# main.net
KiCad netlist of a schematic drawn in Altium Designer
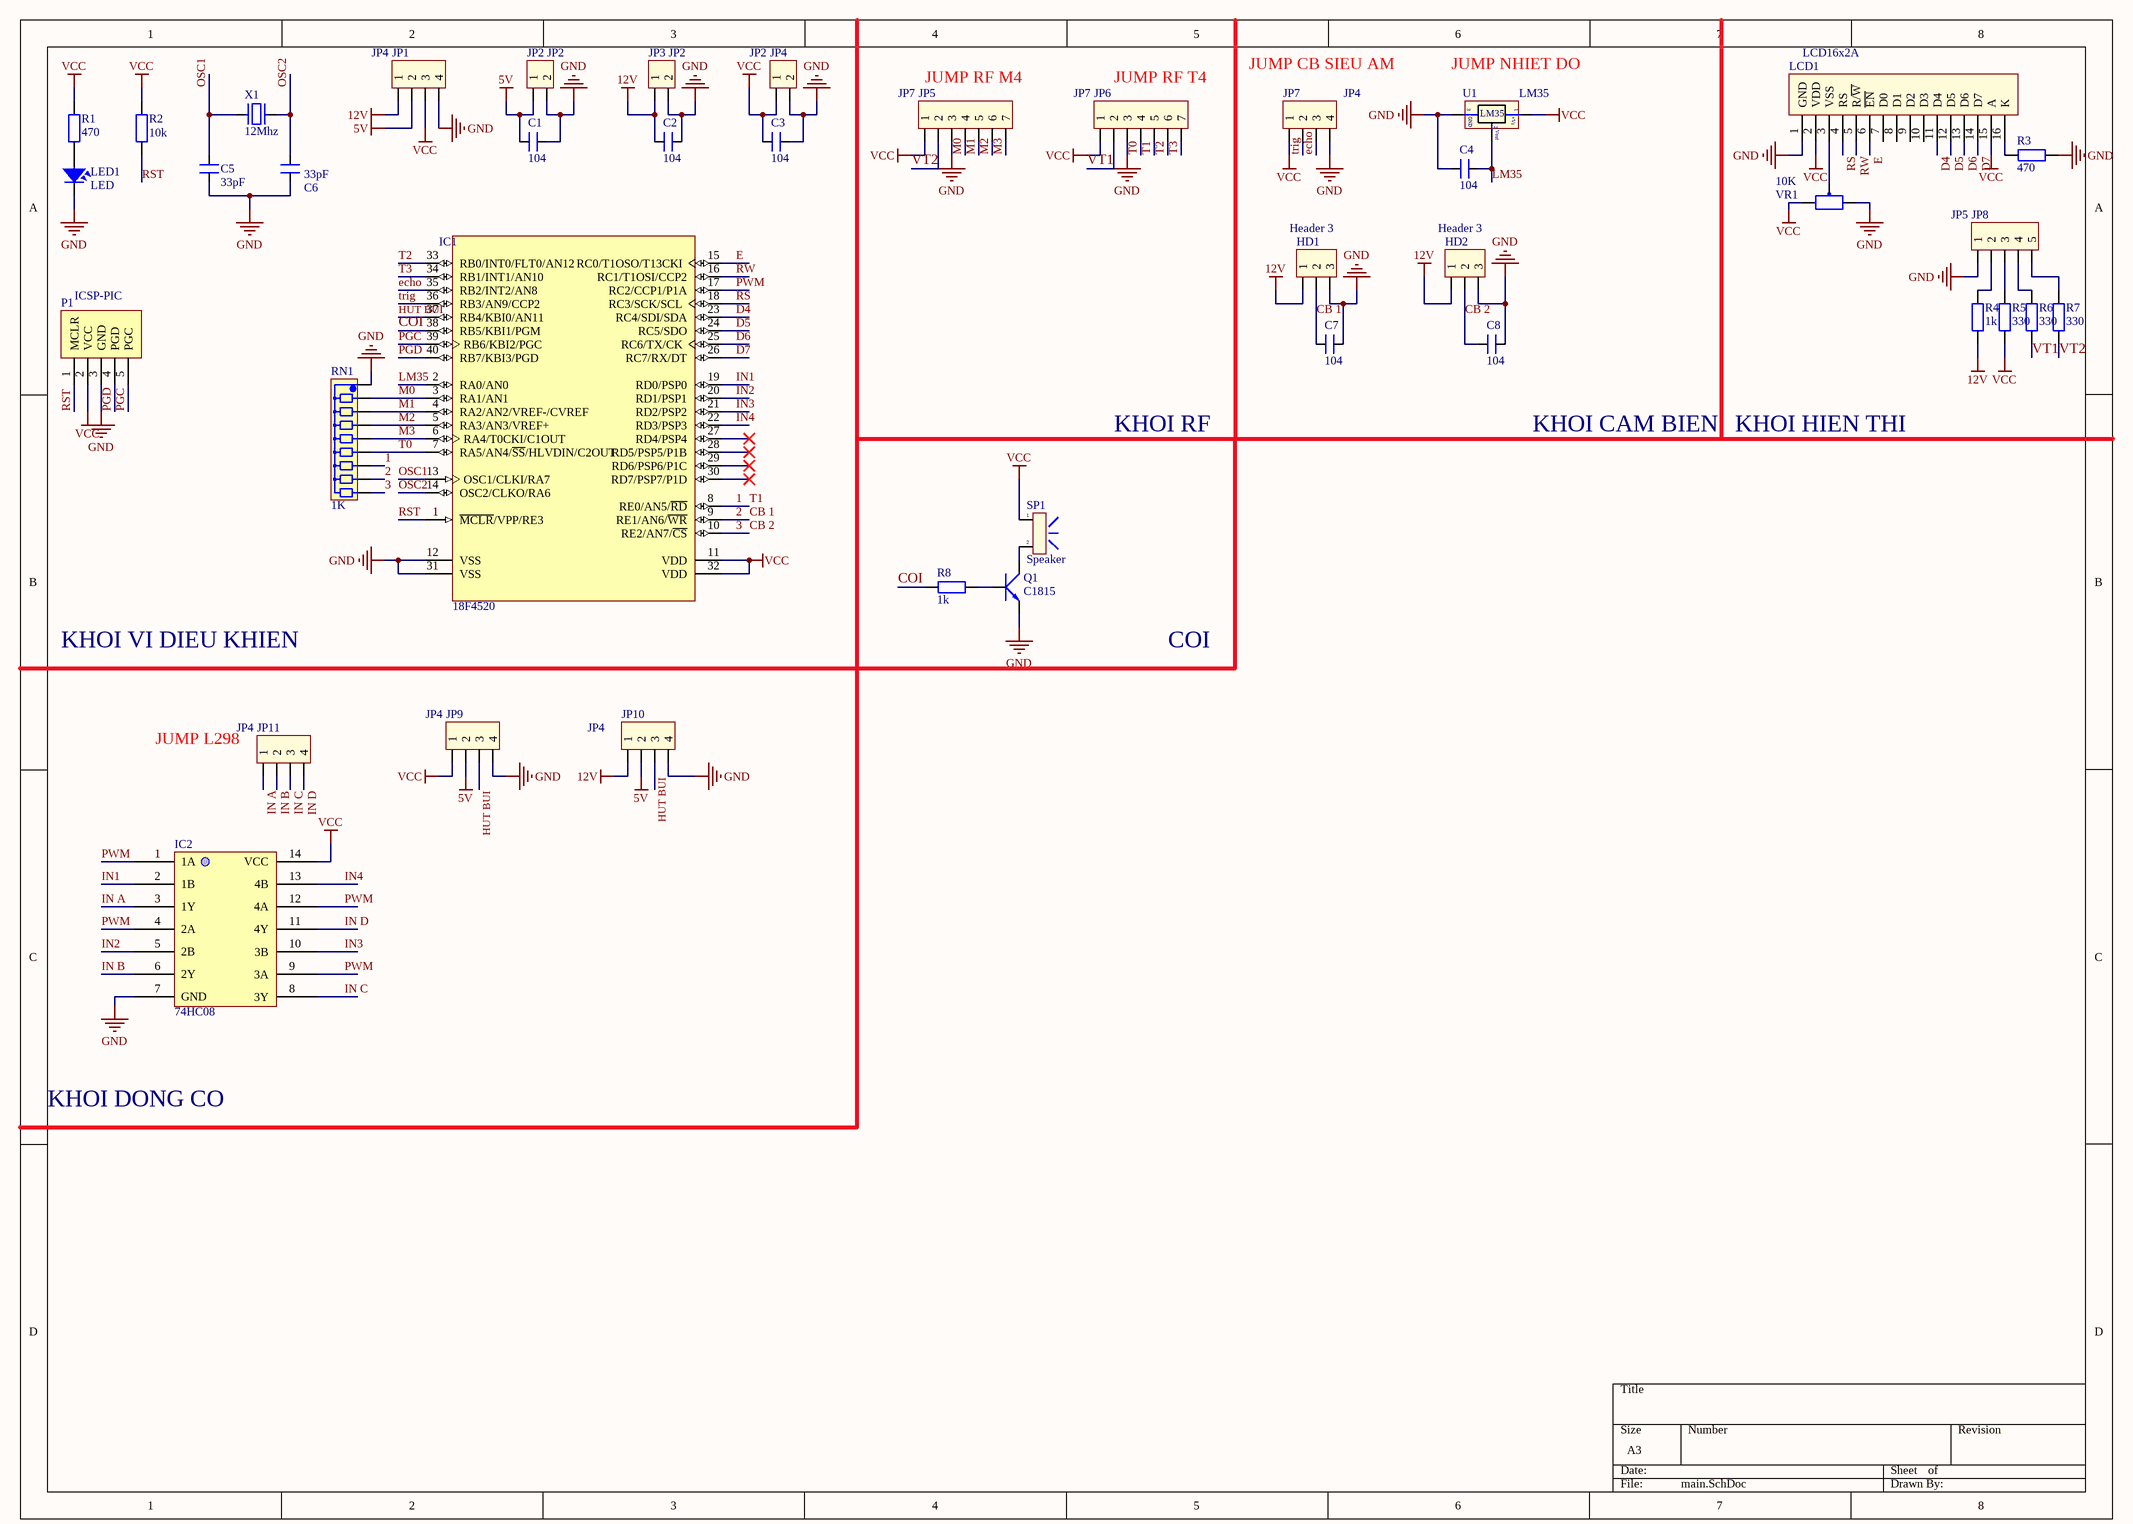
[diagram p0: main.SchDoc]

(export (version "E")
  (design (tool "Eeschema 10.0.6"))
  (components
    (comp (ref "C1")
      (value "104")
      (footprint "CN2")
      (description "Cap np Cremic Value  104pF => 105pF")
      (libsource (lib "syhaunguyen") (part "CN2"))
    )
    (comp (ref "C2")
      (value "104")
      (footprint "CN2")
      (description "Cap np Cremic Value  104pF => 105pF")
      (libsource (lib "syhaunguyen") (part "CN2"))
    )
    (comp (ref "C3")
      (value "104")
      (footprint "CN2")
      (description "Cap np Cremic Value  104pF => 105pF")
      (libsource (lib "syhaunguyen") (part "CN2"))
    )
    (comp (ref "C4")
      (value "104")
      (footprint "CN2")
      (description "Cap np Cremic Value  104pF => 105pF")
      (libsource (lib "syhaunguyen") (part "CN2"))
    )
    (comp (ref "C5")
      (value "33pF")
      (footprint "CN1")
      (description "Cap np Cremic Value  1pF => 472 pF")
      (libsource (lib "syhaunguyen") (part "CN1"))
    )
    (comp (ref "C6")
      (value "33pF")
      (footprint "CN1")
      (description "Cap np Cremic Value  1pF => 472 pF")
      (libsource (lib "syhaunguyen") (part "CN1"))
    )
    (comp (ref "C7")
      (value "104")
      (footprint "CN2")
      (description "Cap np Cremic Value  104pF => 105pF")
      (libsource (lib "syhaunguyen") (part "CN2"))
    )
    (comp (ref "C8")
      (value "104")
      (footprint "CN2")
      (description "Cap np Cremic Value  104pF => 105pF")
      (libsource (lib "syhaunguyen") (part "CN2"))
    )
    (comp (ref "HD1")
      (value "Header 3")
      (footprint "HED3")
      (description "Header 3 (Green)")
      (libsource (lib "syhaunguyen") (part "Hed3"))
    )
    (comp (ref "HD2")
      (value "Header 3")
      (footprint "HED3")
      (description "Header 3 (Green)")
      (libsource (lib "syhaunguyen") (part "Hed3"))
    )
    (comp (ref "IC1")
      (value "18F4520")
      (footprint "DIP40/W0.6")
      (description "32KB Flash, 1536B RAM, 256B EFROM, 40-Pin PDIP")
      (fields (field (name "COPYRIGHT BY") "VanDungEvn"))
      (libsource (lib "syhaunguyen") (part "18F4520"))
    )
    (comp (ref "IC2")
      (value "74HC08")
      (footprint "DIP14/W0.3")
      (libsource (lib "syhaunguyen") (part "74HC08"))
    )
    (comp (ref "JP1")
      (value "JP4")
      (footprint "CON4")
      (description "Connector 4")
      (libsource (lib "") (part "Con4_1"))
    )
    (comp (ref "JP2")
      (value "JP2")
      (footprint "CON2")
      (description "Connector 2")
      (libsource (lib "syhaunguyen") (part "Con2"))
    )
    (comp (ref "JP3")
      (value "JP2")
      (footprint "CON2")
      (description "Connector 2")
      (libsource (lib "syhaunguyen") (part "Con2"))
    )
    (comp (ref "JP4")
      (value "JP2")
      (footprint "CON2")
      (description "Connector 2")
      (libsource (lib "syhaunguyen") (part "Con2"))
    )
    (comp (ref "JP5")
      (value "JP7")
      (footprint "CON7")
      (description "Connector 7")
      (libsource (lib "syhaunguyen") (part "Con7"))
    )
    (comp (ref "JP6")
      (value "JP7")
      (footprint "CON7")
      (description "Connector 7")
      (libsource (lib "syhaunguyen") (part "Con7"))
    )
    (comp (ref "JP7")
      (value "JP4")
      (footprint "CON4")
      (description "Connector 4")
      (libsource (lib "syhaunguyen") (part "Con4"))
    )
    (comp (ref "JP8")
      (value "JP5")
      (footprint "CON5")
      (description "Connector 5")
      (libsource (lib "syhaunguyen") (part "Con5"))
    )
    (comp (ref "JP9")
      (value "JP4")
      (footprint "CON4")
      (description "Connector 4")
      (libsource (lib "") (part "Con4_1"))
    )
    (comp (ref "JP10")
      (value "JP4")
      (footprint "CON4")
      (description "Connector 4")
      (libsource (lib "") (part "Con4_1"))
    )
    (comp (ref "JP11")
      (value "JP4")
      (footprint "CON4")
      (description "Connector 4")
      (libsource (lib "") (part "Con4_1"))
    )
    (comp (ref "LCD1")
      (value "LCD16x2A")
      (footprint "LCD16X2")
      (description "LCD dipslay 16 char, 2 line")
      (libsource (lib "syhaunguyen") (part "LCD16x2"))
    )
    (comp (ref "LED1")
      (value "LED")
      (footprint "LED-3")
      (description "Led  Vuong")
      (libsource (lib "syhaunguyen") (part "LED"))
    )
    (comp (ref "P1")
      (value "ICSP-PIC")
      (footprint "HDR1X5")
      (description "Header, 5-Pin")
      (fields (field (name "PUBLISHER") "Altium Limited"))
      (libsource (lib "Cty1") (part "ICSP-PIC"))
    )
    (comp (ref "Q1")
      (value "C1815")
      (footprint "QTO-92")
      (description "NPN 600mW, ECB")
      (libsource (lib "syhaunguyen") (part "C1815"))
    )
    (comp (ref "R1")
      (value "470")
      (footprint "R1/4W")
      (description "Resistor 1/4W")
      (libsource (lib "syhaunguyen") (part "R1/4W"))
    )
    (comp (ref "R2")
      (value "10k")
      (footprint "R1/4W")
      (description "Resistor 1/4W")
      (libsource (lib "syhaunguyen") (part "R1/4W"))
    )
    (comp (ref "R3")
      (value "470")
      (footprint "R1/4W")
      (description "Resistor 1/4W")
      (libsource (lib "syhaunguyen") (part "R1/4W"))
    )
    (comp (ref "R4")
      (value "1k")
      (footprint "R1/4W")
      (description "Resistor 1/4W")
      (libsource (lib "syhaunguyen") (part "R1/4W"))
    )
    (comp (ref "R5")
      (value "330")
      (footprint "R1/4W")
      (description "Resistor 1/4W")
      (libsource (lib "syhaunguyen") (part "R1/4W"))
    )
    (comp (ref "R6")
      (value "330")
      (footprint "R1/4W")
      (description "Resistor 1/4W")
      (libsource (lib "syhaunguyen") (part "R1/4W"))
    )
    (comp (ref "R7")
      (value "330")
      (footprint "R1/4W")
      (description "Resistor 1/4W")
      (libsource (lib "syhaunguyen") (part "R1/4W"))
    )
    (comp (ref "R8")
      (value "1k")
      (footprint "R1/4W")
      (description "Resistor 1/4W")
      (libsource (lib "syhaunguyen") (part "R1/4W"))
    )
    (comp (ref "RN1")
      (value "1K")
      (footprint "RN8")
      (description "Resistor 8 (Thanh)")
      (libsource (lib "syhaunguyen") (part "RN8"))
    )
    (comp (ref "SP1")
      (value "Speaker")
      (footprint "SPK")
      (description "Speaker Chip")
      (libsource (lib "syhaunguyen") (part "SPK"))
    )
    (comp (ref "U1")
      (value "LM35")
      (footprint "QTO-92")
      (description "Teminal")
      (libsource (lib "syhaunguyen") (part "LM35"))
    )
    (comp (ref "VR1")
      (value "10K")
      (footprint "VR1")
      (description "Var Resistor")
      (libsource (lib "syhaunguyen") (part "VR"))
    )
    (comp (ref "X1")
      (value "12Mhz")
      (footprint "XT2")
      (description "Crystal For all Crystal 2pin.")
      (libsource (lib "syhaunguyen") (part "XT2"))
    )
  )
  (nets
    (net (code "1") (name "/1") (class "Default")
      (node (ref "IC1") (pin "8") (pinfunction "RE0/AN5/~{RD}_8") (pintype "bidirectional"))
      (node (ref "JP6") (pin "5") (pinfunction "5_5") (pintype "passive"))
      (node (ref "RN1") (pin "7") (pinfunction "7_7") (pintype "passive"))
    )
    (net (code "2") (name "/2") (class "Default")
      (node (ref "C7") (pin "1") (pinfunction "1_1") (pintype "passive"))
      (node (ref "HD1") (pin "2") (pinfunction "2_2") (pintype "passive"))
      (node (ref "IC1") (pin "9") (pinfunction "RE1/AN6/~{WR}_9") (pintype "bidirectional"))
      (node (ref "RN1") (pin "8") (pinfunction "8_8") (pintype "passive"))
    )
    (net (code "3") (name "/3") (class "Default")
      (node (ref "C8") (pin "1") (pinfunction "1_1") (pintype "passive"))
      (node (ref "HD2") (pin "2") (pinfunction "2_2") (pintype "passive"))
      (node (ref "IC1") (pin "10") (pinfunction "RE2/AN7/~{CS}_10") (pintype "bidirectional"))
      (node (ref "RN1") (pin "9") (pinfunction "9_9") (pintype "passive"))
    )
    (net (code "4") (name "/COI") (class "Default")
      (node (ref "IC1") (pin "38") (pinfunction "RB5/KBI1/PGM_38") (pintype "bidirectional"))
      (node (ref "R8") (pin "1") (pinfunction "1_1") (pintype "passive"))
    )
    (net (code "5") (name "/D4") (class "Default")
      (node (ref "IC1") (pin "23") (pinfunction "RC4/SDI/SDA_23") (pintype "bidirectional"))
      (node (ref "LCD1") (pin "11") (pinfunction "D4_11") (pintype "passive"))
    )
    (net (code "6") (name "/D5") (class "Default")
      (node (ref "IC1") (pin "24") (pinfunction "RC5/SDO_24") (pintype "bidirectional"))
      (node (ref "LCD1") (pin "12") (pinfunction "D5_12") (pintype "passive"))
    )
    (net (code "7") (name "/D6") (class "Default")
      (node (ref "IC1") (pin "25") (pinfunction "RC6/TX/CK_25") (pintype "bidirectional"))
      (node (ref "LCD1") (pin "13") (pinfunction "D6_13") (pintype "passive"))
    )
    (net (code "8") (name "/D7") (class "Default")
      (node (ref "IC1") (pin "26") (pinfunction "RC7/RX/DT_26") (pintype "bidirectional"))
      (node (ref "LCD1") (pin "14") (pinfunction "D7_14") (pintype "passive"))
    )
    (net (code "9") (name "/E") (class "Default")
      (node (ref "IC1") (pin "15") (pinfunction "RC0/T1OSO/T13CKI_15") (pintype "bidirectional"))
      (node (ref "LCD1") (pin "6") (pinfunction "~{EN}_6") (pintype "passive"))
    )
    (net (code "10") (name "/HUT BUI") (class "Default")
      (node (ref "IC1") (pin "37") (pinfunction "RB4/KBI0/AN11_37") (pintype "bidirectional"))
      (node (ref "JP10") (pin "3") (pinfunction "3_3") (pintype "passive"))
      (node (ref "JP9") (pin "3") (pinfunction "3_3") (pintype "passive"))
    )
    (net (code "11") (name "/IN A") (class "Default")
      (node (ref "IC2") (pin "3") (pinfunction "1Y_3") (pintype "passive"))
      (node (ref "JP11") (pin "1") (pinfunction "1_1") (pintype "passive"))
    )
    (net (code "12") (name "/IN B") (class "Default")
      (node (ref "IC2") (pin "6") (pinfunction "2Y_6") (pintype "passive"))
      (node (ref "JP11") (pin "2") (pinfunction "2_2") (pintype "passive"))
    )
    (net (code "13") (name "/IN C") (class "Default")
      (node (ref "IC2") (pin "8") (pinfunction "3Y_8") (pintype "passive"))
      (node (ref "JP11") (pin "3") (pinfunction "3_3") (pintype "passive"))
    )
    (net (code "14") (name "/IN D") (class "Default")
      (node (ref "IC2") (pin "11") (pinfunction "4Y_11") (pintype "passive"))
      (node (ref "JP11") (pin "4") (pinfunction "4_4") (pintype "passive"))
    )
    (net (code "15") (name "/IN1") (class "Default")
      (node (ref "IC1") (pin "19") (pinfunction "RD0/PSP0_19") (pintype "bidirectional"))
      (node (ref "IC2") (pin "2") (pinfunction "1B_2") (pintype "passive"))
    )
    (net (code "16") (name "/IN2") (class "Default")
      (node (ref "IC1") (pin "20") (pinfunction "RD1/PSP1_20") (pintype "bidirectional"))
      (node (ref "IC2") (pin "5") (pinfunction "2B_5") (pintype "passive"))
    )
    (net (code "17") (name "/IN3") (class "Default")
      (node (ref "IC1") (pin "21") (pinfunction "RD2/PSP2_21") (pintype "bidirectional"))
      (node (ref "IC2") (pin "10") (pinfunction "3B_10") (pintype "passive"))
    )
    (net (code "18") (name "/IN4") (class "Default")
      (node (ref "IC1") (pin "22") (pinfunction "RD3/PSP3_22") (pintype "bidirectional"))
      (node (ref "IC2") (pin "13") (pinfunction "4B_13") (pintype "passive"))
    )
    (net (code "19") (name "/LM35") (class "Default")
      (node (ref "C4") (pin "1") (pinfunction "1_1") (pintype "passive"))
      (node (ref "IC1") (pin "2") (pinfunction "RA0/AN0_2") (pintype "bidirectional"))
      (node (ref "U1") (pin "2") (pinfunction "Vout_2") (pintype "passive"))
    )
    (net (code "20") (name "/M0") (class "Default")
      (node (ref "IC1") (pin "3") (pinfunction "RA1/AN1_3") (pintype "bidirectional"))
      (node (ref "JP5") (pin "4") (pinfunction "4_4") (pintype "passive"))
      (node (ref "RN1") (pin "2") (pinfunction "2_2") (pintype "passive"))
    )
    (net (code "21") (name "/M1") (class "Default")
      (node (ref "IC1") (pin "4") (pinfunction "RA2/AN2/VREF-/CVREF_4") (pintype "bidirectional"))
      (node (ref "JP5") (pin "5") (pinfunction "5_5") (pintype "passive"))
      (node (ref "RN1") (pin "3") (pinfunction "3_3") (pintype "passive"))
    )
    (net (code "22") (name "/M2") (class "Default")
      (node (ref "IC1") (pin "5") (pinfunction "RA3/AN3/VREF+_5") (pintype "bidirectional"))
      (node (ref "JP5") (pin "6") (pinfunction "6_6") (pintype "passive"))
      (node (ref "RN1") (pin "4") (pinfunction "4_4") (pintype "passive"))
    )
    (net (code "23") (name "/M3") (class "Default")
      (node (ref "IC1") (pin "6") (pinfunction "RA4/T0CKI/C1OUT_6") (pintype "bidirectional"))
      (node (ref "JP5") (pin "7") (pinfunction "7_7") (pintype "passive"))
      (node (ref "RN1") (pin "5") (pinfunction "5_5") (pintype "passive"))
    )
    (net (code "24") (name "/OSC1") (class "Default")
      (node (ref "C5") (pin "1") (pinfunction "1_1") (pintype "passive"))
      (node (ref "IC1") (pin "13") (pinfunction "OSC1/CLKI/RA7_13") (pintype "input"))
      (node (ref "X1") (pin "2") (pinfunction "2_2") (pintype "passive"))
    )
    (net (code "25") (name "/OSC2") (class "Default")
      (node (ref "C6") (pin "1") (pinfunction "1_1") (pintype "passive"))
      (node (ref "IC1") (pin "14") (pinfunction "OSC2/CLKO/RA6_14") (pintype "bidirectional"))
      (node (ref "X1") (pin "1") (pinfunction "1_1") (pintype "passive"))
    )
    (net (code "26") (name "/PGC") (class "Default")
      (node (ref "IC1") (pin "39") (pinfunction "RB6/KBI2/PGC_39") (pintype "bidirectional"))
      (node (ref "P1") (pin "5") (pinfunction "PGC_5") (pintype "passive"))
    )
    (net (code "27") (name "/PGD") (class "Default")
      (node (ref "IC1") (pin "40") (pinfunction "RB7/KBI3/PGD_40") (pintype "bidirectional"))
      (node (ref "P1") (pin "4") (pinfunction "PGD_4") (pintype "passive"))
    )
    (net (code "28") (name "/PWM") (class "Default")
      (node (ref "IC1") (pin "17") (pinfunction "RC2/CCP1/P1A_17") (pintype "bidirectional"))
      (node (ref "IC2") (pin "1") (pinfunction "1A_1") (pintype "passive"))
      (node (ref "IC2") (pin "12") (pinfunction "4A_12") (pintype "passive"))
      (node (ref "IC2") (pin "4") (pinfunction "2A_4") (pintype "passive"))
      (node (ref "IC2") (pin "9") (pinfunction "3A_9") (pintype "passive"))
    )
    (net (code "29") (name "/RS") (class "Default")
      (node (ref "IC1") (pin "18") (pinfunction "RC3/SCK/SCL_18") (pintype "bidirectional"))
      (node (ref "LCD1") (pin "4") (pinfunction "RS_4") (pintype "passive"))
    )
    (net (code "30") (name "/RST") (class "Default")
      (node (ref "IC1") (pin "1") (pinfunction "~{MCLR}/VPP/RE3_1") (pintype "input"))
      (node (ref "P1") (pin "1") (pinfunction "MCLR_1") (pintype "passive"))
      (node (ref "R2") (pin "1") (pinfunction "1_1") (pintype "passive"))
    )
    (net (code "31") (name "/RW") (class "Default")
      (node (ref "IC1") (pin "16") (pinfunction "RC1/T1OSI/CCP2_16") (pintype "bidirectional"))
      (node (ref "LCD1") (pin "5") (pinfunction "R/~{W}_5") (pintype "passive"))
    )
    (net (code "32") (name "/T0") (class "Default")
      (node (ref "IC1") (pin "7") (pinfunction "RA5/AN4/~{SS}/HLVDIN/C2OUT_7") (pintype "bidirectional"))
      (node (ref "JP6") (pin "4") (pinfunction "4_4") (pintype "passive"))
      (node (ref "RN1") (pin "6") (pinfunction "6_6") (pintype "passive"))
    )
    (net (code "33") (name "/T2") (class "Default")
      (node (ref "IC1") (pin "33") (pinfunction "RB0/INT0/FLT0/AN12_33") (pintype "bidirectional"))
      (node (ref "JP6") (pin "6") (pinfunction "6_6") (pintype "passive"))
    )
    (net (code "34") (name "/T3") (class "Default")
      (node (ref "IC1") (pin "34") (pinfunction "RB1/INT1/AN10_34") (pintype "bidirectional"))
      (node (ref "JP6") (pin "7") (pinfunction "7_7") (pintype "passive"))
    )
    (net (code "35") (name "/VT1") (class "Default")
      (node (ref "JP6") (pin "2") (pinfunction "2_2") (pintype "passive"))
      (node (ref "R6") (pin "1") (pinfunction "1_1") (pintype "passive"))
    )
    (net (code "36") (name "/VT2") (class "Default")
      (node (ref "JP5") (pin "2") (pinfunction "2_2") (pintype "passive"))
      (node (ref "R7") (pin "1") (pinfunction "1_1") (pintype "passive"))
    )
    (net (code "37") (name "/echo") (class "Default")
      (node (ref "IC1") (pin "35") (pinfunction "RB2/INT2/AN8_35") (pintype "bidirectional"))
      (node (ref "JP7") (pin "3") (pinfunction "3_3") (pintype "passive"))
    )
    (net (code "38") (name "/trig") (class "Default")
      (node (ref "IC1") (pin "36") (pinfunction "RB3/AN9/CCP2_36") (pintype "bidirectional"))
      (node (ref "JP7") (pin "2") (pinfunction "2_2") (pintype "passive"))
    )
    (net (code "39") (name "5V") (class "Default")
      (node (ref "C1") (pin "1") (pinfunction "1_1") (pintype "passive"))
      (node (ref "JP1") (pin "2") (pinfunction "2_2") (pintype "passive"))
      (node (ref "JP10") (pin "2") (pinfunction "2_2") (pintype "passive"))
      (node (ref "JP2") (pin "1") (pinfunction "1_1") (pintype "passive"))
      (node (ref "JP9") (pin "2") (pinfunction "2_2") (pintype "passive"))
    )
    (net (code "40") (name "12V") (class "Default")
      (node (ref "C2") (pin "1") (pinfunction "1_1") (pintype "passive"))
      (node (ref "HD1") (pin "1") (pinfunction "1_1") (pintype "passive"))
      (node (ref "HD2") (pin "1") (pinfunction "1_1") (pintype "passive"))
      (node (ref "JP1") (pin "1") (pinfunction "1_1") (pintype "passive"))
      (node (ref "JP10") (pin "1") (pinfunction "1_1") (pintype "passive"))
      (node (ref "JP3") (pin "1") (pinfunction "1_1") (pintype "passive"))
      (node (ref "R4") (pin "1") (pinfunction "1_1") (pintype "passive"))
    )
    (net (code "41") (name "GND") (class "Default")
      (node (ref "C1") (pin "2") (pinfunction "2_2") (pintype "passive"))
      (node (ref "C2") (pin "2") (pinfunction "2_2") (pintype "passive"))
      (node (ref "C3") (pin "2") (pinfunction "2_2") (pintype "passive"))
      (node (ref "C4") (pin "2") (pinfunction "2_2") (pintype "passive"))
      (node (ref "C5") (pin "2") (pinfunction "2_2") (pintype "passive"))
      (node (ref "C6") (pin "2") (pinfunction "2_2") (pintype "passive"))
      (node (ref "C7") (pin "2") (pinfunction "2_2") (pintype "passive"))
      (node (ref "C8") (pin "2") (pinfunction "2_2") (pintype "passive"))
      (node (ref "HD1") (pin "3") (pinfunction "3_3") (pintype "passive"))
      (node (ref "HD2") (pin "3") (pinfunction "3_3") (pintype "passive"))
      (node (ref "IC1") (pin "12") (pinfunction "VSS_12") (pintype "power_in"))
      (node (ref "IC1") (pin "31") (pinfunction "VSS_31") (pintype "power_in"))
      (node (ref "IC2") (pin "7") (pinfunction "GND_7") (pintype "passive"))
      (node (ref "JP1") (pin "4") (pinfunction "4_4") (pintype "passive"))
      (node (ref "JP10") (pin "4") (pinfunction "4_4") (pintype "passive"))
      (node (ref "JP2") (pin "2") (pinfunction "2_2") (pintype "passive"))
      (node (ref "JP3") (pin "2") (pinfunction "2_2") (pintype "passive"))
      (node (ref "JP4") (pin "2") (pinfunction "2_2") (pintype "passive"))
      (node (ref "JP5") (pin "3") (pinfunction "3_3") (pintype "passive"))
      (node (ref "JP6") (pin "3") (pinfunction "3_3") (pintype "passive"))
      (node (ref "JP7") (pin "4") (pinfunction "4_4") (pintype "passive"))
      (node (ref "JP8") (pin "1") (pinfunction "1_1") (pintype "passive"))
      (node (ref "JP9") (pin "4") (pinfunction "4_4") (pintype "passive"))
      (node (ref "LCD1") (pin "1") (pinfunction "GND_1") (pintype "passive"))
      (node (ref "LED1") (pin "2") (pinfunction "2_2") (pintype "passive"))
      (node (ref "P1") (pin "3") (pinfunction "GND_3") (pintype "passive"))
      (node (ref "Q1") (pin "1") (pinfunction "E_1") (pintype "passive"))
      (node (ref "R3") (pin "1") (pinfunction "1_1") (pintype "passive"))
      (node (ref "RN1") (pin "1") (pinfunction "1_1") (pintype "passive"))
      (node (ref "U1") (pin "3") (pinfunction "-_3") (pintype "passive"))
      (node (ref "VR1") (pin "3") (pinfunction "3_3") (pintype "passive"))
    )
    (net (code "42") (name "Net-(JP8-Pad2)") (class "Default")
      (node (ref "JP8") (pin "2") (pinfunction "2_2") (pintype "passive"))
      (node (ref "R4") (pin "2") (pinfunction "2_2") (pintype "passive"))
    )
    (net (code "43") (name "Net-(JP8-Pad3)") (class "Default")
      (node (ref "JP8") (pin "3") (pinfunction "3_3") (pintype "passive"))
      (node (ref "R5") (pin "2") (pinfunction "2_2") (pintype "passive"))
    )
    (net (code "44") (name "Net-(JP8-Pad4)") (class "Default")
      (node (ref "JP8") (pin "4") (pinfunction "4_4") (pintype "passive"))
      (node (ref "R6") (pin "2") (pinfunction "2_2") (pintype "passive"))
    )
    (net (code "45") (name "Net-(JP8-Pad5)") (class "Default")
      (node (ref "JP8") (pin "5") (pinfunction "5_5") (pintype "passive"))
      (node (ref "R7") (pin "2") (pinfunction "2_2") (pintype "passive"))
    )
    (net (code "46") (name "Net-(LCD1-K)") (class "Default")
      (node (ref "LCD1") (pin "16") (pinfunction "K_16") (pintype "passive"))
      (node (ref "R3") (pin "2") (pinfunction "2_2") (pintype "passive"))
    )
    (net (code "47") (name "Net-(LCD1-VSS)") (class "Default")
      (node (ref "LCD1") (pin "3") (pinfunction "VSS_3") (pintype "passive"))
      (node (ref "VR1") (pin "2") (pinfunction "2_2") (pintype "passive"))
    )
    (net (code "48") (name "Net-(LED1-Pad1)") (class "Default")
      (node (ref "LED1") (pin "1") (pinfunction "1_1") (pintype "passive"))
      (node (ref "R1") (pin "2") (pinfunction "2_2") (pintype "passive"))
    )
    (net (code "49") (name "Net-(Q1-B)") (class "Default")
      (node (ref "Q1") (pin "3") (pinfunction "B_3") (pintype "passive"))
      (node (ref "R8") (pin "2") (pinfunction "2_2") (pintype "passive"))
    )
    (net (code "50") (name "Net-(Q1-C)") (class "Default")
      (node (ref "Q1") (pin "2") (pinfunction "C_2") (pintype "passive"))
      (node (ref "SP1") (pin "2") (pinfunction "2_2") (pintype "passive"))
    )
    (net (code "51") (name "VCC") (class "Default")
      (node (ref "C3") (pin "1") (pinfunction "1_1") (pintype "passive"))
      (node (ref "IC1") (pin "11") (pinfunction "VDD_11") (pintype "power_in"))
      (node (ref "IC1") (pin "32") (pinfunction "VDD_32") (pintype "power_in"))
      (node (ref "IC2") (pin "14") (pinfunction "VCC_14") (pintype "passive"))
      (node (ref "JP1") (pin "3") (pinfunction "3_3") (pintype "passive"))
      (node (ref "JP4") (pin "1") (pinfunction "1_1") (pintype "passive"))
      (node (ref "JP5") (pin "1") (pinfunction "1_1") (pintype "passive"))
      (node (ref "JP6") (pin "1") (pinfunction "1_1") (pintype "passive"))
      (node (ref "JP7") (pin "1") (pinfunction "1_1") (pintype "passive"))
      (node (ref "JP9") (pin "1") (pinfunction "1_1") (pintype "passive"))
      (node (ref "LCD1") (pin "15") (pinfunction "A_15") (pintype "passive"))
      (node (ref "LCD1") (pin "2") (pinfunction "VDD_2") (pintype "passive"))
      (node (ref "P1") (pin "2") (pinfunction "VCC_2") (pintype "passive"))
      (node (ref "R1") (pin "1") (pinfunction "1_1") (pintype "passive"))
      (node (ref "R2") (pin "2") (pinfunction "2_2") (pintype "passive"))
      (node (ref "R5") (pin "1") (pinfunction "1_1") (pintype "passive"))
      (node (ref "SP1") (pin "1") (pinfunction "1_1") (pintype "passive"))
      (node (ref "U1") (pin "1") (pinfunction "+Vs_1") (pintype "passive"))
      (node (ref "VR1") (pin "1") (pinfunction "1_1") (pintype "passive"))
    )
    (net (code "52") (name "unconnected-(IC1-RD4{slash}PSP4-Pad27)") (class "Default")
      (node (ref "IC1") (pin "27") (pinfunction "RD4/PSP4_27") (pintype "bidirectional+no_connect"))
    )
    (net (code "53") (name "unconnected-(IC1-RD5{slash}PSP5{slash}P1B-Pad28)") (class "Default")
      (node (ref "IC1") (pin "28") (pinfunction "RD5/PSP5/P1B_28") (pintype "bidirectional+no_connect"))
    )
    (net (code "54") (name "unconnected-(IC1-RD6{slash}PSP6{slash}P1C-Pad29)") (class "Default")
      (node (ref "IC1") (pin "29") (pinfunction "RD6/PSP6/P1C_29") (pintype "bidirectional+no_connect"))
    )
    (net (code "55") (name "unconnected-(IC1-RD7{slash}PSP7{slash}P1D-Pad30)") (class "Default")
      (node (ref "IC1") (pin "30") (pinfunction "RD7/PSP7/P1D_30") (pintype "bidirectional+no_connect"))
    )
    (net (code "56") (name "unconnected-(LCD1-D0-Pad7)") (class "Default")
      (node (ref "LCD1") (pin "7") (pinfunction "D0_7") (pintype "passive"))
    )
    (net (code "57") (name "unconnected-(LCD1-D1-Pad8)") (class "Default")
      (node (ref "LCD1") (pin "8") (pinfunction "D1_8") (pintype "passive"))
    )
    (net (code "58") (name "unconnected-(LCD1-D2-Pad9)") (class "Default")
      (node (ref "LCD1") (pin "9") (pinfunction "D2_9") (pintype "passive"))
    )
    (net (code "59") (name "unconnected-(LCD1-D3-Pad10)") (class "Default")
      (node (ref "LCD1") (pin "10") (pinfunction "D3_10") (pintype "passive"))
    )
  )
)
